# f1_Not.net
KiCad netlist of a schematic drawn in EAGLE
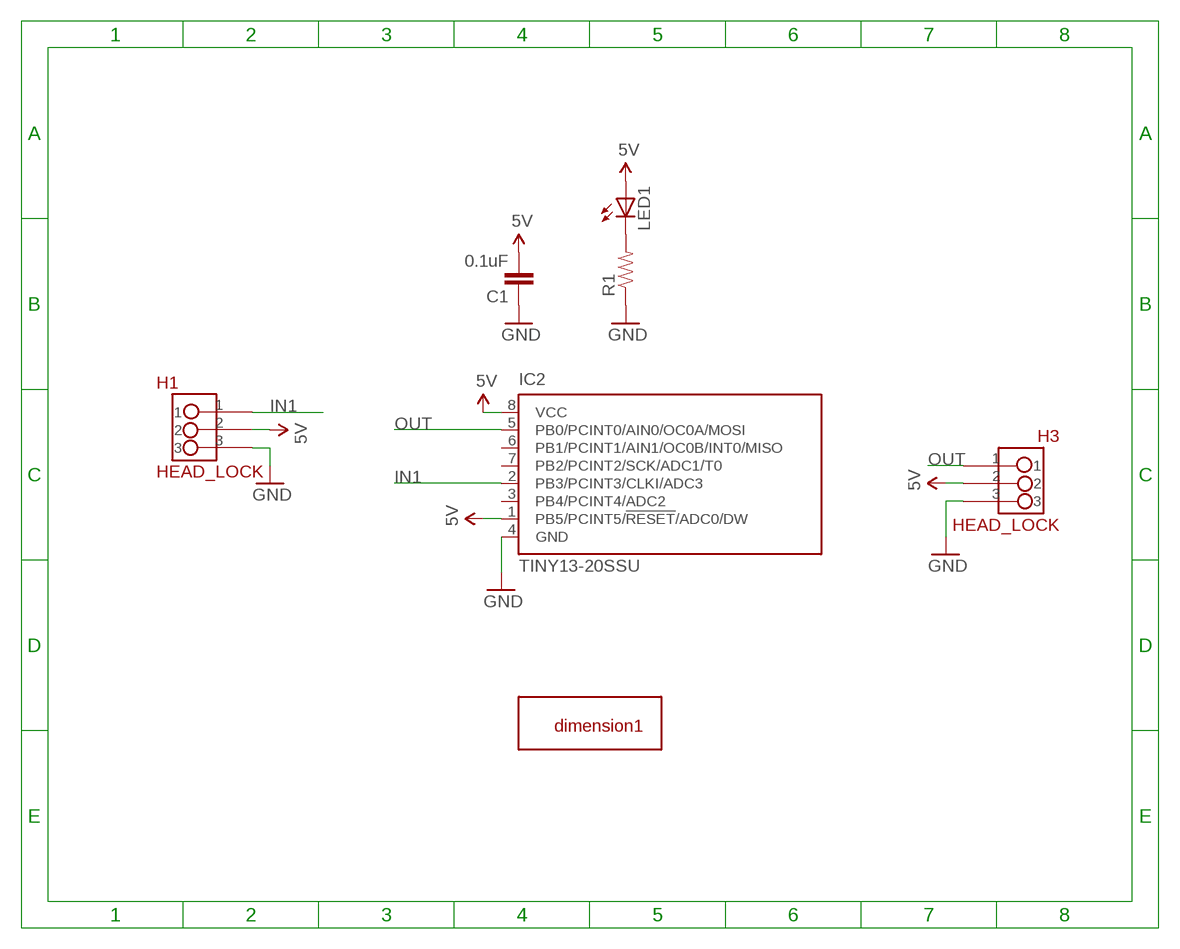
[diagram p0: schematic, sheet 1]

(export (version "E")
  (design (tool "Eeschema 10.0.6"))
  (components
    (comp (ref "C1")
      (value "0.1uF")
      (footprint "eagle-import:0603-CAP")
      (libsource (lib "eagle-import") (part "0.1UF-25V(+80/-20%)(0603)"))
    )
    (comp (ref "H1")
      (value "HEAD_LOCK")
      (footprint "eagle-import:HEAD_LOCK")
      (libsource (lib "eagle-import") (part "HEAD_LOCK"))
    )
    (comp (ref "H3")
      (value "HEAD_LOCK")
      (footprint "eagle-import:HEAD_LOCK")
      (libsource (lib "eagle-import") (part "HEAD_LOCK"))
    )
    (comp (ref "IC2")
      (value "TINY13-20SSU")
      (footprint "eagle-import:8S1")
      (fields (field (name "MPN") "ATTINY13-20SSU"))
      (libsource (lib "eagle-import") (part "TINY13SSU-20"))
    )
    (comp (ref "LED1")
      (value "LEDSML0603")
      (footprint "eagle-import:SML0603")
      (libsource (lib "eagle-import") (part "LEDSML0603"))
    )
    (comp (ref "R1")
      (value "RESISTOR0603-RES")
      (footprint "eagle-import:0603-RES")
      (libsource (lib "eagle-import") (part "RESISTOR0603-RES"))
    )
    (comp (ref "U$1")
      (value "DIMENSION1")
      (footprint "eagle-import:DIMENSION1")
      (libsource (lib "eagle-import") (part "DIMENSION1"))
    )
  )
  (nets
    (net (code "1") (name "/IN1") (class "Default")
      (node (ref "H1") (pin "1") (pinfunction "1_1") (pintype "passive"))
      (node (ref "IC2") (pin "2") (pinfunction "PB3/PCINT3/CLKI/ADC3_2") (pintype "bidirectional"))
    )
    (net (code "2") (name "/OUT") (class "Default")
      (node (ref "H3") (pin "1") (pinfunction "1_1") (pintype "passive"))
      (node (ref "IC2") (pin "5") (pinfunction "PB0/PCINT0/AIN0/OC0A/MOSI_5") (pintype "bidirectional"))
    )
    (net (code "3") (name "5V") (class "Default")
      (node (ref "C1") (pin "2") (pinfunction "2_2") (pintype "passive"))
      (node (ref "H1") (pin "2") (pinfunction "2_2") (pintype "passive"))
      (node (ref "H3") (pin "2") (pinfunction "2_2") (pintype "passive"))
      (node (ref "IC2") (pin "1") (pinfunction "PB5/PCINT5/~{RESET}/ADC0/DW_1") (pintype "bidirectional"))
      (node (ref "IC2") (pin "8") (pinfunction "VCC_8") (pintype "power_in"))
      (node (ref "LED1") (pin "A") (pinfunction "A_A") (pintype "passive"))
    )
    (net (code "4") (name "GND") (class "Default")
      (node (ref "C1") (pin "1") (pinfunction "1_1") (pintype "passive"))
      (node (ref "H1") (pin "3") (pinfunction "3_3") (pintype "passive"))
      (node (ref "H3") (pin "3") (pinfunction "3_3") (pintype "passive"))
      (node (ref "IC2") (pin "4") (pinfunction "GND_4") (pintype "power_in"))
      (node (ref "R1") (pin "1") (pinfunction "1_1") (pintype "passive"))
    )
    (net (code "5") (name "Net-(LED1-PadC)") (class "Default")
      (node (ref "LED1") (pin "C") (pinfunction "C_C") (pintype "passive"))
      (node (ref "R1") (pin "2") (pinfunction "2_2") (pintype "passive"))
    )
    (net (code "6") (name "unconnected-(IC2-PB1{slash}PCINT1{slash}AIN1{slash}OC0B{slash}INT0{slash}MISO-Pad6)") (class "Default")
      (node (ref "IC2") (pin "6") (pinfunction "PB1/PCINT1/AIN1/OC0B/INT0/MISO_6") (pintype "bidirectional"))
    )
    (net (code "7") (name "unconnected-(IC2-PB2{slash}PCINT2{slash}SCK{slash}ADC1{slash}T0-Pad7)") (class "Default")
      (node (ref "IC2") (pin "7") (pinfunction "PB2/PCINT2/SCK/ADC1/T0_7") (pintype "bidirectional"))
    )
    (net (code "8") (name "unconnected-(IC2-PB4{slash}PCINT4{slash}ADC2-Pad3)") (class "Default")
      (node (ref "IC2") (pin "3") (pinfunction "PB4/PCINT4/ADC2_3") (pintype "bidirectional"))
    )
  )
)
